# power.net
KiCad netlist of a schematic drawn in Altium Designer
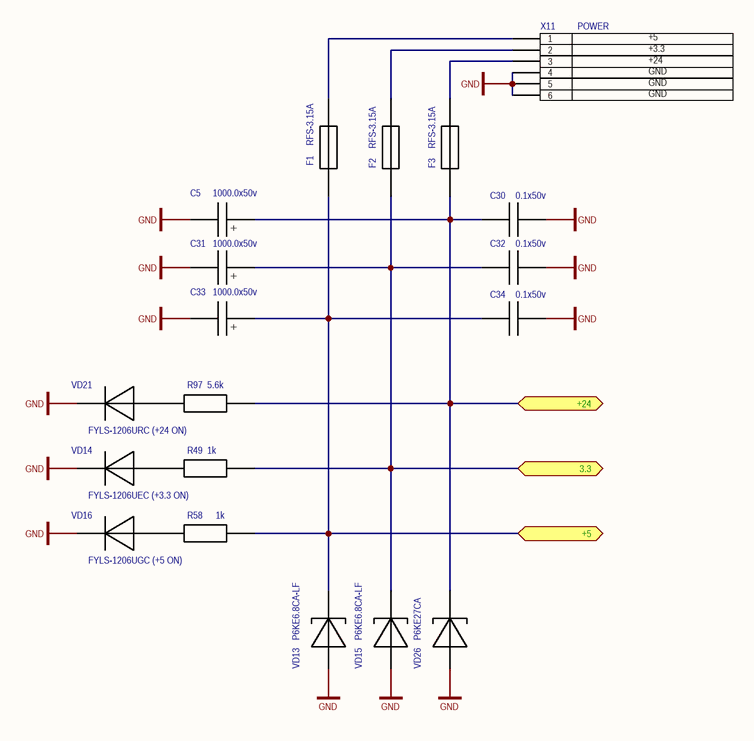
[diagram p0: power.SchDoc]

(export (version "E")
  (design (tool "Eeschema 10.0.6"))
  (components
    (comp (ref "C5")
      (value "1000.0x50v")
      (footprint "C-LOW-ESR-16-18")
      (description "Выводной электролит")
      (libsource (lib "ulysses_library") (part "C-LOW-ESR-RADIAL"))
    )
    (comp (ref "C30")
      (value "0.1x50v")
      (footprint "CAPC3216X05N")
      (description "SMD конденсатор")
      (libsource (lib "ulysses_library") (part "C"))
    )
    (comp (ref "C31")
      (value "1000.0x50v")
      (footprint "C-LOW-ESR-16-18")
      (description "Выводной электролит")
      (libsource (lib "ulysses_library") (part "C-LOW-ESR-RADIAL"))
    )
    (comp (ref "C32")
      (value "0.1x50v")
      (footprint "CAPC3216X05N")
      (description "SMD конденсатор")
      (libsource (lib "ulysses_library") (part "C"))
    )
    (comp (ref "C33")
      (value "1000.0x50v")
      (footprint "C-LOW-ESR-16-18")
      (description "Выводной электролит")
      (libsource (lib "ulysses_library") (part "C-LOW-ESR-RADIAL"))
    )
    (comp (ref "C34")
      (value "0.1x50v")
      (footprint "CAPC3216X05N")
      (description "SMD конденсатор")
      (libsource (lib "ulysses_library") (part "C"))
    )
    (comp (ref "F1")
      (value "RFS-3.15A")
      (footprint "MRT-FUSE")
      (description "Вставка плавкая")
      (libsource (lib "ulysses_library") (part "FUSE"))
    )
    (comp (ref "F2")
      (value "RFS-3.15A")
      (footprint "MRT-FUSE")
      (description "Вставка плавкая")
      (libsource (lib "ulysses_library") (part "FUSE"))
    )
    (comp (ref "F3")
      (value "RFS-3.15A")
      (footprint "MRT-FUSE")
      (description "Вставка плавкая")
      (libsource (lib "ulysses_library") (part "FUSE"))
    )
    (comp (ref "R49")
      (value "1k")
      (footprint "RESC2012X04N")
      (description "SMD резистор")
      (libsource (lib "ulysses_library") (part "R"))
    )
    (comp (ref "R58")
      (value "1k")
      (footprint "RESC2012X04N")
      (description "SMD резистор")
      (libsource (lib "ulysses_library") (part "R"))
    )
    (comp (ref "R97")
      (value "5.6k")
      (footprint "RESC2012X04N")
      (description "SMD резистор")
      (libsource (lib "ulysses_library") (part "R"))
    )
    (comp (ref "VD13")
      (value "P6KE6.8CA-LF")
      (footprint "P6KE27CA")
      (description "Cупрессор")
      (libsource (lib "ulysses_library") (part "P6KE27CA"))
    )
    (comp (ref "VD14")
      (value "FYLS-1206UEC (+3.3 ON)")
      (footprint "CAPMP3216X11N")
      (description "Светодиод")
      (libsource (lib "ulysses_library") (part "FYLS-1206"))
    )
    (comp (ref "VD15")
      (value "P6KE6.8CA-LF")
      (footprint "P6KE27CA")
      (description "Cупрессор")
      (libsource (lib "ulysses_library") (part "P6KE27CA"))
    )
    (comp (ref "VD16")
      (value "FYLS-1206UGC (+5 ON)")
      (footprint "CAPMP3216X11N")
      (description "Светодиод")
      (libsource (lib "ulysses_library") (part "FYLS-1206"))
    )
    (comp (ref "VD21")
      (value "FYLS-1206URC (+24 ON)")
      (footprint "CAPMP3216X11N")
      (description "Светодиод")
      (libsource (lib "ulysses_library") (part "FYLS-1206"))
    )
    (comp (ref "VD26")
      (value "P6KE27CA")
      (footprint "P6KE27CA")
      (description "Cупрессор")
      (libsource (lib "ulysses_library") (part "P6KE27CA"))
    )
    (comp (ref "X11")
      (value "POWER")
      (footprint "MINI-FIT-6WAY-SM")
      (libsource (lib "ulysses_library") (part "MINI-FIT-6-WAY-M"))
    )
  )
  (nets
    (net (code "1") (name "/+5") (class "Default")
      (node (ref "C33") (pin "1") (pinfunction "+_1") (pintype "passive"))
      (node (ref "C34") (pin "1") (pinfunction "1_1") (pintype "passive"))
      (node (ref "F1") (pin "1") (pinfunction "1_1") (pintype "passive"))
      (node (ref "R58") (pin "2") (pinfunction "2_2") (pintype "passive"))
      (node (ref "VD13") (pin "K") (pinfunction "K_K") (pintype "passive"))
    )
    (net (code "2") (name "/+24") (class "Default")
      (node (ref "C30") (pin "1") (pinfunction "1_1") (pintype "passive"))
      (node (ref "C5") (pin "1") (pinfunction "+_1") (pintype "passive"))
      (node (ref "F3") (pin "1") (pinfunction "1_1") (pintype "passive"))
      (node (ref "R97") (pin "2") (pinfunction "2_2") (pintype "passive"))
      (node (ref "VD26") (pin "K") (pinfunction "K_K") (pintype "passive"))
    )
    (net (code "3") (name "/3.3") (class "Default")
      (node (ref "C31") (pin "1") (pinfunction "+_1") (pintype "passive"))
      (node (ref "C32") (pin "1") (pinfunction "1_1") (pintype "passive"))
      (node (ref "F2") (pin "1") (pinfunction "1_1") (pintype "passive"))
      (node (ref "R49") (pin "2") (pinfunction "2_2") (pintype "passive"))
      (node (ref "VD15") (pin "K") (pinfunction "K_K") (pintype "passive"))
    )
    (net (code "4") (name "GND") (class "Default")
      (node (ref "C30") (pin "2") (pinfunction "2_2") (pintype "passive"))
      (node (ref "C31") (pin "2") (pinfunction "2_2") (pintype "passive"))
      (node (ref "C32") (pin "2") (pinfunction "2_2") (pintype "passive"))
      (node (ref "C33") (pin "2") (pinfunction "2_2") (pintype "passive"))
      (node (ref "C34") (pin "2") (pinfunction "2_2") (pintype "passive"))
      (node (ref "C5") (pin "2") (pinfunction "2_2") (pintype "passive"))
      (node (ref "VD13") (pin "A") (pinfunction "A_A") (pintype "passive"))
      (node (ref "VD14") (pin "1") (pinfunction "C_1") (pintype "power_in"))
      (node (ref "VD15") (pin "A") (pinfunction "A_A") (pintype "passive"))
      (node (ref "VD16") (pin "1") (pinfunction "C_1") (pintype "power_in"))
      (node (ref "VD21") (pin "1") (pinfunction "C_1") (pintype "power_in"))
      (node (ref "VD26") (pin "A") (pinfunction "A_A") (pintype "passive"))
      (node (ref "X11") (pin "4") (pinfunction "4_4") (pintype "passive"))
      (node (ref "X11") (pin "5") (pinfunction "5_5") (pintype "passive"))
      (node (ref "X11") (pin "6") (pinfunction "6_6") (pintype "passive"))
    )
    (net (code "5") (name "Net-(F1-Pad2)") (class "Default")
      (node (ref "F1") (pin "2") (pinfunction "2_2") (pintype "passive"))
      (node (ref "X11") (pin "1") (pinfunction "1_1") (pintype "passive"))
    )
    (net (code "6") (name "Net-(F2-Pad2)") (class "Default")
      (node (ref "F2") (pin "2") (pinfunction "2_2") (pintype "passive"))
      (node (ref "X11") (pin "2") (pinfunction "2_2") (pintype "passive"))
    )
    (net (code "7") (name "Net-(F3-Pad2)") (class "Default")
      (node (ref "F3") (pin "2") (pinfunction "2_2") (pintype "passive"))
      (node (ref "X11") (pin "3") (pinfunction "3_3") (pintype "passive"))
    )
    (net (code "8") (name "Net-(VD14-A)") (class "Default")
      (node (ref "R49") (pin "1") (pintype "passive"))
      (node (ref "VD14") (pin "2") (pinfunction "A_2") (pintype "power_in"))
    )
    (net (code "9") (name "Net-(VD16-A)") (class "Default")
      (node (ref "R58") (pin "1") (pintype "passive"))
      (node (ref "VD16") (pin "2") (pinfunction "A_2") (pintype "power_in"))
    )
    (net (code "10") (name "Net-(VD21-A)") (class "Default")
      (node (ref "R97") (pin "1") (pintype "passive"))
      (node (ref "VD21") (pin "2") (pinfunction "A_2") (pintype "power_in"))
    )
  )
)
